# MPU_HMC.net
KiCad netlist of a schematic drawn in Altium Designer
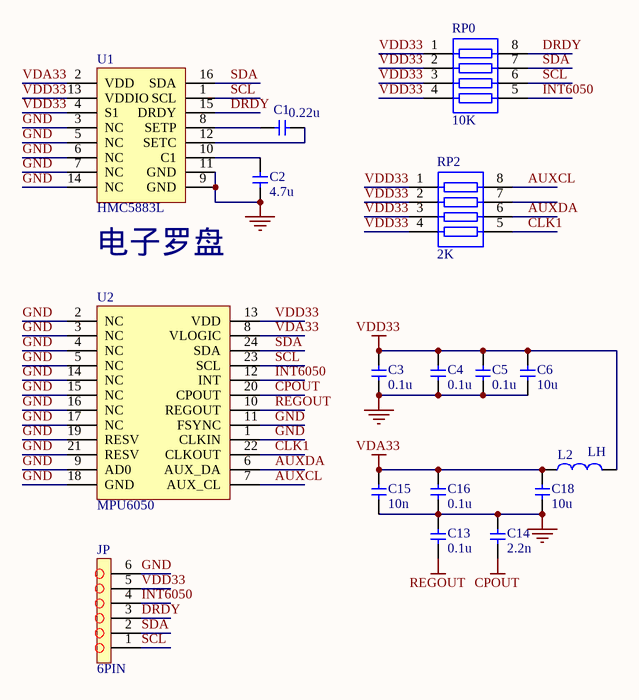
[diagram p0: MPU_HMC.SchDoc]

(export (version "E")
  (design (tool "Eeschema 10.0.6"))
  (components
    (comp (ref "C1") (value "0.22u") (footprint "RC100") (libsource (lib "*") (part "CAPA")))
    (comp (ref "C2") (value "4.7u") (footprint "RC100") (libsource (lib "*") (part "CAPA")))
    (comp (ref "C3") (value "0.1u") (footprint "RC100") (libsource (lib "*") (part "CAPA")))
    (comp (ref "C4") (value "0.1u") (footprint "RC100") (libsource (lib "*") (part "CAPA")))
    (comp (ref "C5") (value "0.1u") (footprint "RC100") (libsource (lib "*") (part "CAPA")))
    (comp (ref "C6") (value "10u") (footprint "RC100") (libsource (lib "*") (part "CAPA")))
    (comp (ref "C13") (value "0.1u") (footprint "RC100") (libsource (lib "*") (part "CAPA")))
    (comp (ref "C14") (value "2.2n") (footprint "RC100") (libsource (lib "*") (part "CAPA")))
    (comp (ref "C15") (value "10n") (footprint "RC100") (libsource (lib "*") (part "CAPA")))
    (comp (ref "C16") (value "0.1u") (footprint "RC100") (libsource (lib "*") (part "CAPA")))
    (comp (ref "C18") (value "10u") (footprint "RC100") (libsource (lib "*") (part "CAPA")))
    (comp (ref "JP") (value "6PIN") (footprint "SIP6") (libsource (lib "Common") (part "6PIN")))
    (comp (ref "L2") (value "LH") (footprint "1206") (libsource (lib "*") (part "LH")))
    (comp (ref "RP0") (value "10K") (footprint "RN4") (libsource (lib "*") (part "RESPACK4")))
    (comp (ref "RP2") (value "2K") (footprint "RN4") (libsource (lib "*") (part "RESPACK4")))
    (comp (ref "U1") (value "HMC5883L") (footprint "LPCC-16") (libsource (lib "*") (part "HMC5883L")))
    (comp (ref "U2") (value "MPU6050") (footprint "QFN-24") (libsource (lib "*") (part "MPU6050")))
  )
  (nets
    (net (code "1") (name "/AUXCL") (class "Default")
      (node (ref "RP2") (pin "8") (pintype "passive"))
      (node (ref "U2") (pin "7") (pinfunction "AUX_CL_7") (pintype "passive"))
    )
    (net (code "2") (name "/AUXDA") (class "Default")
      (node (ref "RP2") (pin "6") (pintype "passive"))
      (node (ref "U2") (pin "6") (pinfunction "AUX_DA_6") (pintype "passive"))
    )
    (net (code "3") (name "/CLK1") (class "Default")
      (node (ref "RP2") (pin "5") (pintype "passive"))
      (node (ref "U2") (pin "22") (pinfunction "CLKOUT_22") (pintype "passive"))
    )
    (net (code "4") (name "/DRDY") (class "Default")
      (node (ref "JP") (pin "3") (pintype "passive"))
      (node (ref "RP0") (pin "8") (pintype "passive"))
      (node (ref "U1") (pin "15") (pinfunction "DRDY_15") (pintype "passive"))
    )
    (net (code "5") (name "/INT6050") (class "Default")
      (node (ref "JP") (pin "4") (pintype "passive"))
      (node (ref "RP0") (pin "5") (pintype "passive"))
      (node (ref "U2") (pin "12") (pinfunction "INT_12") (pintype "passive"))
    )
    (net (code "6") (name "/SCL") (class "Default")
      (node (ref "JP") (pin "1") (pintype "passive"))
      (node (ref "RP0") (pin "6") (pintype "passive"))
      (node (ref "U1") (pin "1") (pinfunction "SCL_1") (pintype "passive"))
      (node (ref "U2") (pin "23") (pinfunction "SCL_23") (pintype "passive"))
    )
    (net (code "7") (name "/SDA") (class "Default")
      (node (ref "JP") (pin "2") (pintype "passive"))
      (node (ref "RP0") (pin "7") (pintype "passive"))
      (node (ref "U1") (pin "16") (pinfunction "SDA_16") (pintype "passive"))
      (node (ref "U2") (pin "24") (pinfunction "SDA_24") (pintype "passive"))
    )
    (net (code "8") (name "CPOUT") (class "Default")
      (node (ref "C14") (pin "1") (pintype "passive"))
      (node (ref "U2") (pin "20") (pinfunction "CPOUT_20") (pintype "passive"))
    )
    (net (code "9") (name "GND") (class "Default")
      (node (ref "C13") (pin "2") (pintype "passive"))
      (node (ref "C14") (pin "2") (pintype "passive"))
      (node (ref "C15") (pin "1") (pintype "passive"))
      (node (ref "C16") (pin "2") (pintype "passive"))
      (node (ref "C18") (pin "2") (pintype "passive"))
      (node (ref "C2") (pin "1") (pintype "passive"))
      (node (ref "C3") (pin "1") (pintype "passive"))
      (node (ref "C4") (pin "1") (pintype "passive"))
      (node (ref "C5") (pin "2") (pintype "passive"))
      (node (ref "C6") (pin "2") (pintype "passive"))
      (node (ref "JP") (pin "6") (pintype "passive"))
      (node (ref "U1") (pin "11") (pinfunction "GND_11") (pintype "passive"))
      (node (ref "U1") (pin "14") (pinfunction "NC_14") (pintype "passive"))
      (node (ref "U1") (pin "3") (pinfunction "NC_3") (pintype "passive"))
      (node (ref "U1") (pin "5") (pinfunction "NC_5") (pintype "passive"))
      (node (ref "U1") (pin "6") (pinfunction "NC_6") (pintype "passive"))
      (node (ref "U1") (pin "7") (pinfunction "NC_7") (pintype "passive"))
      (node (ref "U1") (pin "9") (pinfunction "GND_9") (pintype "passive"))
      (node (ref "U2") (pin "1") (pinfunction "CLKIN_1") (pintype "passive"))
      (node (ref "U2") (pin "11") (pinfunction "FSYNC_11") (pintype "passive"))
      (node (ref "U2") (pin "14") (pinfunction "NC_14") (pintype "passive"))
      (node (ref "U2") (pin "15") (pinfunction "NC_15") (pintype "passive"))
      (node (ref "U2") (pin "16") (pinfunction "NC_16") (pintype "passive"))
      (node (ref "U2") (pin "17") (pinfunction "NC_17") (pintype "passive"))
      (node (ref "U2") (pin "18") (pinfunction "GND_18") (pintype "passive"))
      (node (ref "U2") (pin "19") (pinfunction "RESV_19") (pintype "passive"))
      (node (ref "U2") (pin "2") (pinfunction "NC_2") (pintype "passive"))
      (node (ref "U2") (pin "21") (pinfunction "RESV_21") (pintype "passive"))
      (node (ref "U2") (pin "3") (pinfunction "NC_3") (pintype "passive"))
      (node (ref "U2") (pin "4") (pinfunction "NC_4") (pintype "passive"))
      (node (ref "U2") (pin "5") (pinfunction "NC_5") (pintype "passive"))
      (node (ref "U2") (pin "9") (pinfunction "AD0_9") (pintype "passive"))
    )
    (net (code "10") (name "Net-(U1-C1)") (class "Default")
      (node (ref "C2") (pin "2") (pintype "passive"))
      (node (ref "U1") (pin "10") (pinfunction "C1_10") (pintype "passive"))
    )
    (net (code "11") (name "Net-(U1-SETC)") (class "Default")
      (node (ref "C1") (pin "2") (pintype "passive"))
      (node (ref "U1") (pin "12") (pinfunction "SETC_12") (pintype "passive"))
    )
    (net (code "12") (name "Net-(U1-SETP)") (class "Default")
      (node (ref "C1") (pin "1") (pintype "passive"))
      (node (ref "U1") (pin "8") (pinfunction "SETP_8") (pintype "passive"))
    )
    (net (code "13") (name "REGOUT") (class "Default")
      (node (ref "C13") (pin "1") (pintype "passive"))
      (node (ref "U2") (pin "10") (pinfunction "REGOUT_10") (pintype "passive"))
    )
    (net (code "14") (name "VDA33") (class "Default")
      (node (ref "C15") (pin "2") (pintype "passive"))
      (node (ref "C16") (pin "1") (pintype "passive"))
      (node (ref "C18") (pin "1") (pintype "passive"))
      (node (ref "L2") (pin "1") (pintype "passive"))
      (node (ref "U1") (pin "2") (pinfunction "VDD_2") (pintype "passive"))
      (node (ref "U2") (pin "8") (pinfunction "VLOGIC_8") (pintype "passive"))
    )
    (net (code "15") (name "VDD33") (class "Default")
      (node (ref "C3") (pin "2") (pintype "passive"))
      (node (ref "C4") (pin "2") (pintype "passive"))
      (node (ref "C5") (pin "1") (pintype "passive"))
      (node (ref "C6") (pin "1") (pintype "passive"))
      (node (ref "JP") (pin "5") (pintype "passive"))
      (node (ref "L2") (pin "2") (pintype "passive"))
      (node (ref "RP0") (pin "1") (pintype "passive"))
      (node (ref "RP0") (pin "2") (pintype "passive"))
      (node (ref "RP0") (pin "3") (pintype "passive"))
      (node (ref "RP0") (pin "4") (pintype "passive"))
      (node (ref "RP2") (pin "1") (pintype "passive"))
      (node (ref "RP2") (pin "2") (pintype "passive"))
      (node (ref "RP2") (pin "3") (pintype "passive"))
      (node (ref "RP2") (pin "4") (pintype "passive"))
      (node (ref "U1") (pin "13") (pinfunction "VDDIO_13") (pintype "passive"))
      (node (ref "U1") (pin "4") (pinfunction "S1_4") (pintype "passive"))
      (node (ref "U2") (pin "13") (pinfunction "VDD_13") (pintype "passive"))
    )
    (net (code "16") (name "unconnected-(RP2-Pad7)") (class "Default")
      (node (ref "RP2") (pin "7") (pintype "passive"))
    )
  )
)
